# LabAccessBoard.net
KiCad netlist of a schematic drawn in EAGLE
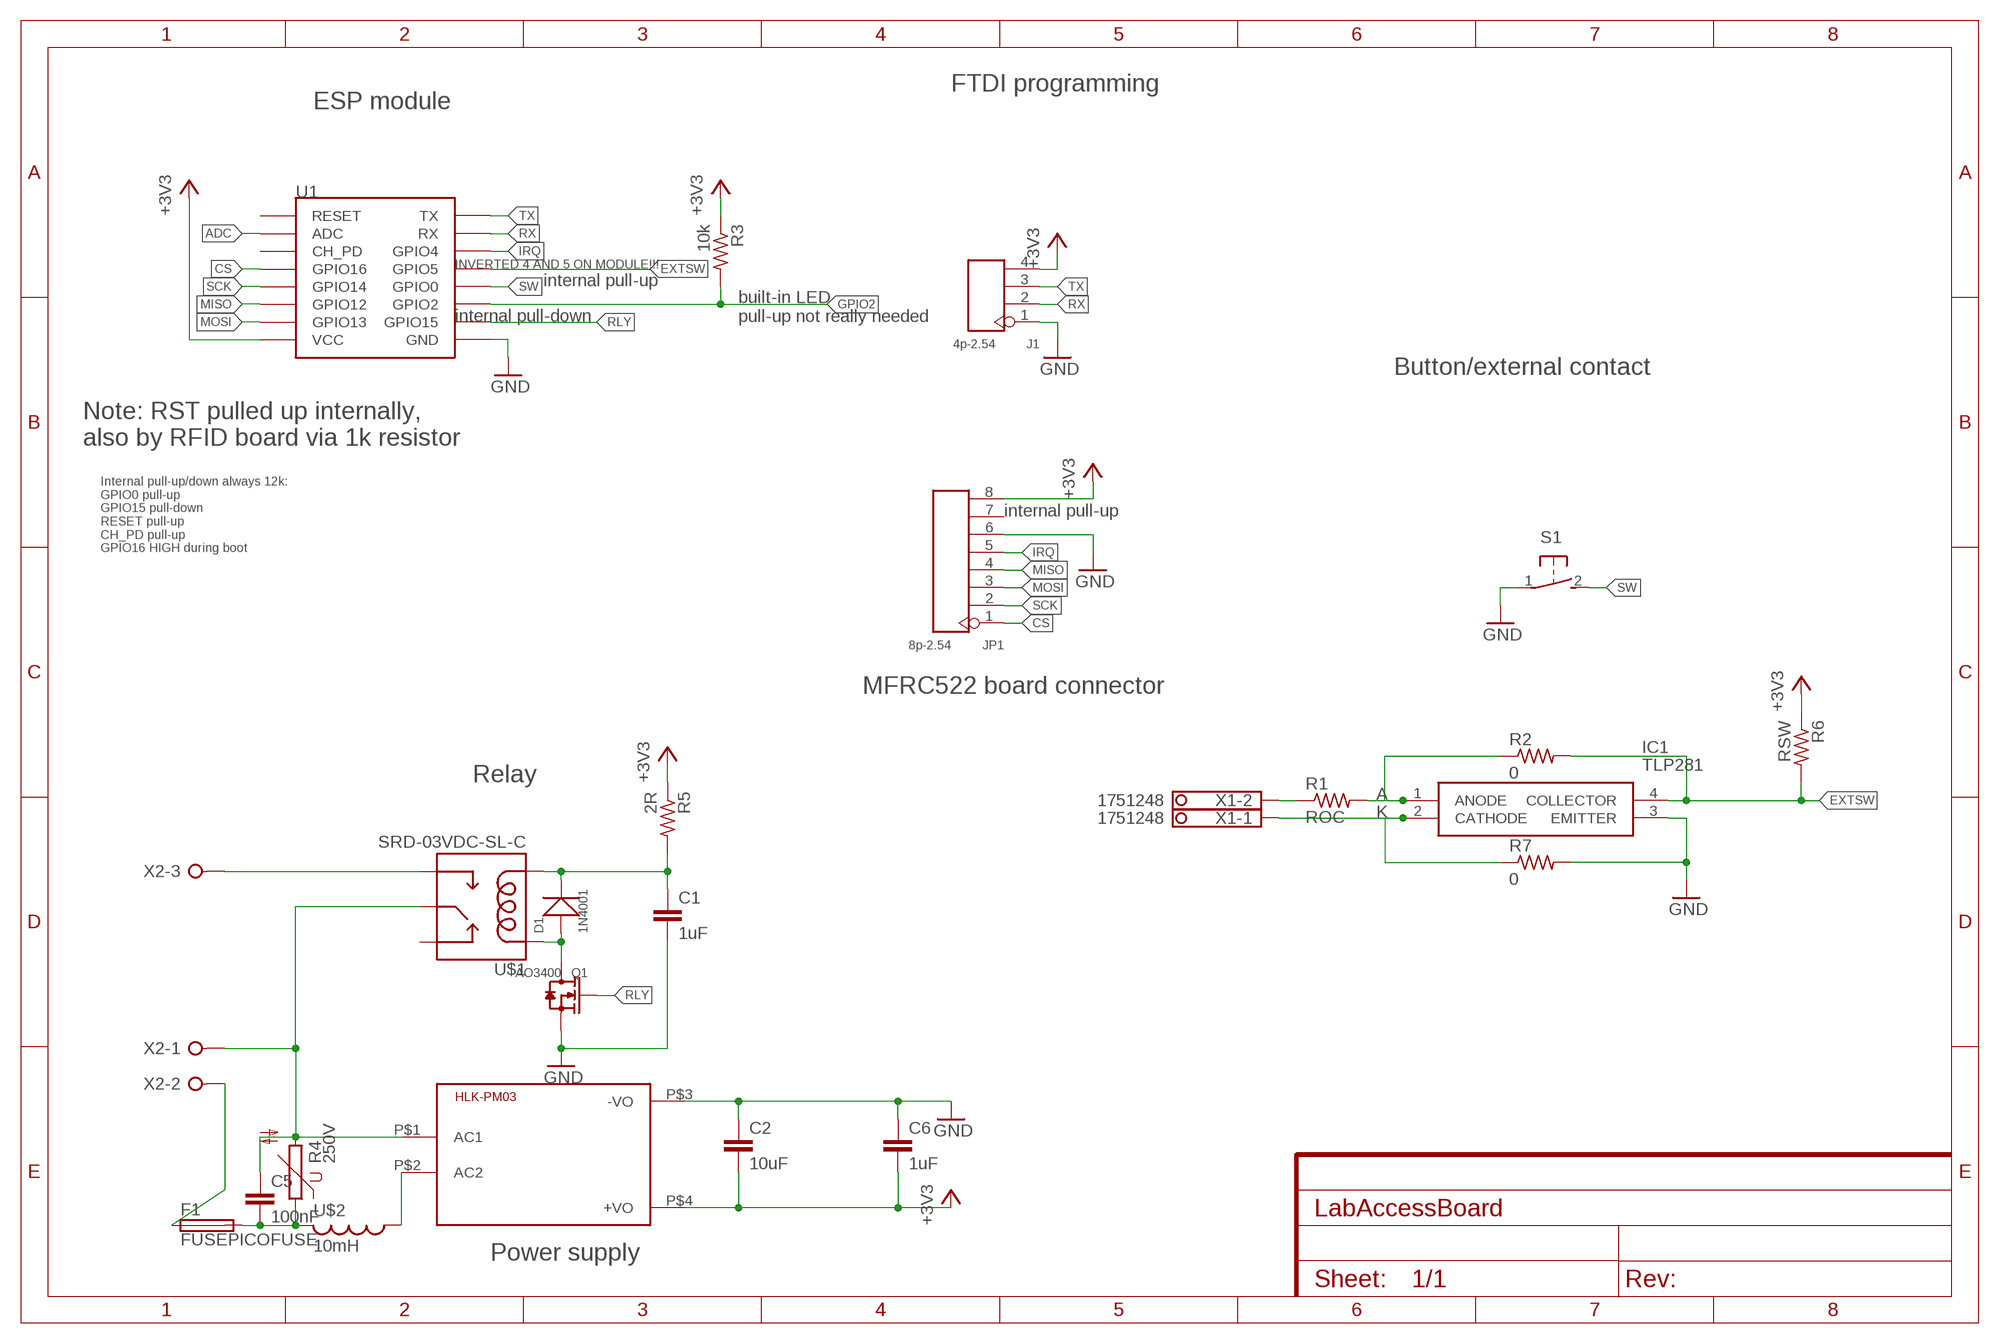
[diagram p0: schematic, sheet 1]

(export (version "E")
  (design (tool "Eeschema 10.0.6"))
  (components
    (comp (ref "C1")
      (value "1uF")
      (footprint "eagle-import:C0603K")
      (libsource (lib "eagle-import") (part "C-EUC0603K"))
    )
    (comp (ref "C2")
      (value "10uF")
      (footprint "eagle-import:C0805K")
      (libsource (lib "eagle-import") (part "C-EUC0805K"))
    )
    (comp (ref "C5")
      (value "100nF")
      (footprint "eagle-import:C102-064X133")
      (libsource (lib "eagle-import") (part "C-EU102-064X133"))
    )
    (comp (ref "C6")
      (value "1uF")
      (footprint "eagle-import:C0603K")
      (libsource (lib "eagle-import") (part "C-EUC0603K"))
    )
    (comp (ref "D1")
      (value "1N4001")
      (footprint "eagle-import:DO-214AC")
      (fields (field (name "MPN") "1N4007"))
      (libsource (lib "eagle-import") (part "DIODE-GEN-PURPOSE-1KV-1A(DO-214AC)"))
    )
    (comp (ref "F1")
      (value "FUSEPICOFUSE")
      (footprint "eagle-import:PICOFUSE")
      (libsource (lib "eagle-import") (part "FUSEPICOFUSE"))
    )
    (comp (ref "HLK-PM03")
      (value "HLK-PM03")
      (footprint "eagle-import:HLK-PM01")
      (libsource (lib "eagle-import") (part "HLK-PM013W"))
    )
    (comp (ref "IC1")
      (value "TLP281")
      (footprint "eagle-import:SOIC127P700X190-4N")
      (fields (field (name "ARROW_PART_NUMBER") "TLP281(GB-TP,F)"))
      (libsource (lib "eagle-import") (part "TLP281(GB-TP,F)"))
    )
    (comp (ref "J1")
      (value "4p-2.54")
      (footprint "eagle-import:H4-2.54")
      (fields (field (name "MPN") "P125-1104A0BS116A1"))
      (libsource (lib "eagle-import") (part "DIP-BLACK-MALE-HEADER-VERT(4P-2.54)"))
    )
    (comp (ref "JP1")
      (value "8p-2.54")
      (footprint "eagle-import:H8-2.54")
      (fields (field (name "MPN") "P125-1108A1BS116A1"))
      (libsource (lib "eagle-import") (part "DIP-BLACK-MALE-HEADER-VERT(8P-2.54)"))
    )
    (comp (ref "Q1")
      (value "AO3400")
      (footprint "eagle-import:SOT-23")
      (fields (field (name "MPN") "2N7002,215"))
      (libsource (lib "eagle-import") (part "SMD-MOSFET-N-CH-60V-300MA-LOGIC-LEVEL-FET-2N7002(SOT-23)"))
    )
    (comp (ref "R1")
      (value "ROC")
      (footprint "eagle-import:R0603")
      (libsource (lib "eagle-import") (part "R-US_R0603"))
    )
    (comp (ref "R2")
      (value "0")
      (footprint "eagle-import:R0603")
      (libsource (lib "eagle-import") (part "R-US_R0603"))
    )
    (comp (ref "R3")
      (value "10k")
      (footprint "eagle-import:R0603")
      (libsource (lib "eagle-import") (part "R-US_R0603"))
    )
    (comp (ref "R4")
      (value "250V")
      (footprint "eagle-import:S07K250")
      (libsource (lib "eagle-import") (part "S07K250"))
    )
    (comp (ref "R5")
      (value "2R")
      (footprint "eagle-import:R0603")
      (libsource (lib "eagle-import") (part "R-US_R0603"))
    )
    (comp (ref "R6")
      (value "RSW")
      (footprint "eagle-import:R0603")
      (libsource (lib "eagle-import") (part "R-US_R0603"))
    )
    (comp (ref "R7")
      (value "0")
      (footprint "eagle-import:R0603")
      (libsource (lib "eagle-import") (part "R-US_R0603"))
    )
    (comp (ref "S1")
      (value "31-XX")
      (footprint "eagle-import:B3F-31XX")
      (fields (field (name "MPN") "B3F-3100"))
      (libsource (lib "eagle-import") (part "31-XX"))
    )
    (comp (ref "U$1")
      (value "SRD-03VDC-SL-C")
      (footprint "eagle-import:SRD-0XVDC-SL-C")
      (libsource (lib "eagle-import") (part "SRD-0XVDC-SL-CSRD-06VDC-SL-C"))
    )
    (comp (ref "U$2")
      (value "10mH")
      (footprint "eagle-import:6000-XXXX-RC")
      (libsource (lib "eagle-import") (part "L-US6000-XXX-RC"))
    )
    (comp (ref "U1")
      (value "ESP12SMD")
      (footprint "eagle-import:ESP12-SMD")
      (libsource (lib "eagle-import") (part "ESP12SMD"))
    )
    (comp (ref "X1")
      (value "1751248")
      (footprint "eagle-import:1751248")
      (libsource (lib "eagle-import") (part "1751248"))
    )
    (comp (ref "X2")
      (value "W237-3E")
      (footprint "eagle-import:W237-3E")
      (libsource (lib "eagle-import") (part "W237-3E"))
    )
  )
  (nets
    (net (code "1") (name "+3V3") (class "Default")
      (node (ref "C2") (pin "2") (pinfunction "2_2") (pintype "passive"))
      (node (ref "C6") (pin "2") (pinfunction "2_2") (pintype "passive"))
      (node (ref "HLK-PM03") (pin "P$4") (pinfunction "+VO_P$4") (pintype "bidirectional"))
      (node (ref "J1") (pin "4") (pinfunction "P$4_4") (pintype "bidirectional"))
      (node (ref "JP1") (pin "8") (pinfunction "8_8") (pintype "bidirectional"))
      (node (ref "R3") (pin "1") (pinfunction "1_1") (pintype "passive"))
      (node (ref "R5") (pin "1") (pinfunction "1_1") (pintype "passive"))
      (node (ref "R6") (pin "1") (pinfunction "1_1") (pintype "passive"))
      (node (ref "U1") (pin "VCC") (pinfunction "VCC_VCC") (pintype "bidirectional"))
    )
    (net (code "2") (name "/A") (class "Default")
      (node (ref "IC1") (pin "1") (pinfunction "ANODE_1") (pintype "bidirectional"))
      (node (ref "R1") (pin "2") (pinfunction "2_2") (pintype "passive"))
      (node (ref "R2") (pin "1") (pinfunction "1_1") (pintype "passive"))
    )
    (net (code "3") (name "/K") (class "Default")
      (node (ref "IC1") (pin "2") (pinfunction "CATHODE_2") (pintype "bidirectional"))
      (node (ref "R7") (pin "1") (pinfunction "1_1") (pintype "passive"))
      (node (ref "X1") (pin "1") (pinfunction "K_1") (pintype "passive"))
    )
    (net (code "4") (name "ADC") (class "Default")
      (node (ref "U1") (pin "ADC") (pinfunction "ADC_ADC") (pintype "bidirectional"))
    )
    (net (code "5") (name "CS") (class "Default")
      (node (ref "JP1") (pin "1") (pinfunction "1_1") (pintype "bidirectional"))
      (node (ref "U1") (pin "GPIO16") (pinfunction "GPIO16_GPIO16") (pintype "bidirectional"))
    )
    (net (code "6") (name "EXTSW") (class "Default")
      (node (ref "IC1") (pin "4") (pinfunction "COLLECTOR_4") (pintype "bidirectional"))
      (node (ref "R2") (pin "2") (pinfunction "2_2") (pintype "passive"))
      (node (ref "R6") (pin "2") (pinfunction "2_2") (pintype "passive"))
      (node (ref "U1") (pin "GPIO5") (pinfunction "GPIO5_GPIO5") (pintype "bidirectional"))
    )
    (net (code "7") (name "GND") (class "Default")
      (node (ref "C1") (pin "2") (pinfunction "2_2") (pintype "passive"))
      (node (ref "C2") (pin "1") (pinfunction "1_1") (pintype "passive"))
      (node (ref "C6") (pin "1") (pinfunction "1_1") (pintype "passive"))
      (node (ref "HLK-PM03") (pin "P$3") (pinfunction "-VO_P$3") (pintype "bidirectional"))
      (node (ref "IC1") (pin "3") (pinfunction "EMITTER_3") (pintype "bidirectional"))
      (node (ref "J1") (pin "1") (pinfunction "P$1_1") (pintype "bidirectional"))
      (node (ref "JP1") (pin "6") (pinfunction "6_6") (pintype "bidirectional"))
      (node (ref "Q1") (pin "2") (pinfunction "S_2") (pintype "passive"))
      (node (ref "R7") (pin "2") (pinfunction "2_2") (pintype "passive"))
      (node (ref "S1") (pin "1") (pinfunction "P_1") (pintype "passive"))
      (node (ref "U1") (pin "GND") (pinfunction "GND_GND") (pintype "bidirectional"))
    )
    (net (code "8") (name "GPIO2") (class "Default")
      (node (ref "R3") (pin "2") (pinfunction "2_2") (pintype "passive"))
      (node (ref "U1") (pin "GPIO2") (pinfunction "GPIO2_GPIO2") (pintype "bidirectional"))
    )
    (net (code "9") (name "IRQ") (class "Default")
      (node (ref "JP1") (pin "5") (pinfunction "5_5") (pintype "bidirectional"))
      (node (ref "U1") (pin "GPIO4") (pinfunction "GPIO4_GPIO4") (pintype "bidirectional"))
    )
    (net (code "10") (name "MISO") (class "Default")
      (node (ref "JP1") (pin "4") (pinfunction "4_4") (pintype "bidirectional"))
      (node (ref "U1") (pin "GPIO12") (pinfunction "GPIO12_GPIO12") (pintype "bidirectional"))
    )
    (net (code "11") (name "MOSI") (class "Default")
      (node (ref "JP1") (pin "3") (pinfunction "3_3") (pintype "bidirectional"))
      (node (ref "U1") (pin "GPIO13") (pinfunction "GPIO13_GPIO13") (pintype "bidirectional"))
    )
    (net (code "12") (name "Net-(C5-Pad2)") (class "Default")
      (node (ref "C5") (pin "2") (pinfunction "2_2") (pintype "passive"))
      (node (ref "F1") (pin "2") (pinfunction "2_2") (pintype "passive"))
      (node (ref "R4") (pin "1") (pinfunction "1_1") (pintype "passive"))
      (node (ref "U$2") (pin "2") (pinfunction "2_2") (pintype "passive"))
    )
    (net (code "13") (name "Net-(D1-+)") (class "Default")
      (node (ref "D1") (pin "1") (pinfunction "+_1") (pintype "passive"))
      (node (ref "Q1") (pin "3") (pinfunction "D_3") (pintype "passive"))
      (node (ref "U$1") (pin "COIL1") (pinfunction "COIL1_COIL1") (pintype "bidirectional"))
    )
    (net (code "14") (name "Net-(D1--)") (class "Default")
      (node (ref "C1") (pin "1") (pinfunction "1_1") (pintype "passive"))
      (node (ref "D1") (pin "2") (pinfunction "-_2") (pintype "passive"))
      (node (ref "R5") (pin "2") (pinfunction "2_2") (pintype "passive"))
      (node (ref "U$1") (pin "COIL0") (pinfunction "COIL0_COIL0") (pintype "bidirectional"))
    )
    (net (code "15") (name "Net-(HLK-PM03-AC1)") (class "Default")
      (node (ref "C5") (pin "1") (pinfunction "1_1") (pintype "passive"))
      (node (ref "HLK-PM03") (pin "P$1") (pinfunction "AC1_P$1") (pintype "bidirectional"))
      (node (ref "R4") (pin "2") (pinfunction "2_2") (pintype "passive"))
      (node (ref "U$1") (pin "SWCOMMON") (pinfunction "SWCOMMON_SWCOMMON") (pintype "bidirectional"))
      (node (ref "X2") (pin "1") (pinfunction "KL_1") (pintype "passive"))
    )
    (net (code "16") (name "Net-(HLK-PM03-AC2)") (class "Default")
      (node (ref "HLK-PM03") (pin "P$2") (pinfunction "AC2_P$2") (pintype "bidirectional"))
      (node (ref "U$2") (pin "1") (pinfunction "1_1") (pintype "passive"))
    )
    (net (code "17") (name "Net-(X1B-K)") (class "Default")
      (node (ref "R1") (pin "1") (pinfunction "1_1") (pintype "passive"))
      (node (ref "X1") (pin "2") (pinfunction "K_2") (pintype "passive"))
    )
    (net (code "18") (name "Net-(X2B-KL)") (class "Default")
      (node (ref "F1") (pin "1") (pinfunction "1_1") (pintype "passive"))
      (node (ref "X2") (pin "2") (pinfunction "KL_2") (pintype "passive"))
    )
    (net (code "19") (name "Net-(X2C-KL)") (class "Default")
      (node (ref "U$1") (pin "SWOPEN") (pinfunction "SWOPEN_SWOPEN") (pintype "bidirectional"))
      (node (ref "X2") (pin "3") (pinfunction "KL_3") (pintype "passive"))
    )
    (net (code "20") (name "RLY") (class "Default")
      (node (ref "Q1") (pin "1") (pinfunction "G_1") (pintype "passive"))
      (node (ref "U1") (pin "GPIO15") (pinfunction "GPIO15_GPIO15") (pintype "bidirectional"))
    )
    (net (code "21") (name "RX") (class "Default")
      (node (ref "J1") (pin "2") (pinfunction "P$2_2") (pintype "bidirectional"))
      (node (ref "U1") (pin "RXD0") (pinfunction "RX_RXD0") (pintype "bidirectional"))
    )
    (net (code "22") (name "SCK") (class "Default")
      (node (ref "JP1") (pin "2") (pinfunction "2_2") (pintype "bidirectional"))
      (node (ref "U1") (pin "GPIO14") (pinfunction "GPIO14_GPIO14") (pintype "bidirectional"))
    )
    (net (code "23") (name "SW") (class "Default")
      (node (ref "S1") (pin "2") (pinfunction "S_2") (pintype "passive"))
      (node (ref "U1") (pin "GPIO0") (pinfunction "GPIO0_GPIO0") (pintype "bidirectional"))
    )
    (net (code "24") (name "TX") (class "Default")
      (node (ref "J1") (pin "3") (pinfunction "P$3_3") (pintype "bidirectional"))
      (node (ref "U1") (pin "TXD0") (pinfunction "TX_TXD0") (pintype "bidirectional"))
    )
    (net (code "25") (name "unconnected-(JP1-Pad7)") (class "Default")
      (node (ref "JP1") (pin "7") (pinfunction "7_7") (pintype "bidirectional"))
    )
    (net (code "26") (name "unconnected-(U$1-SWCLOSE-PadSWCLOSED)") (class "Default")
      (node (ref "U$1") (pin "SWCLOSED") (pinfunction "SWCLOSE_SWCLOSED") (pintype "bidirectional"))
    )
    (net (code "27") (name "unconnected-(U1-PadCH_PD)") (class "Default")
      (node (ref "U1") (pin "CH_PD") (pinfunction "CH_PD_CH_PD") (pintype "bidirectional"))
    )
    (net (code "28") (name "unconnected-(U1-PadRESET)") (class "Default")
      (node (ref "U1") (pin "RESET") (pinfunction "RESET_RESET") (pintype "bidirectional"))
    )
  )
)
